# USB-Serial.net
KiCad netlist of a schematic drawn in Altium Designer
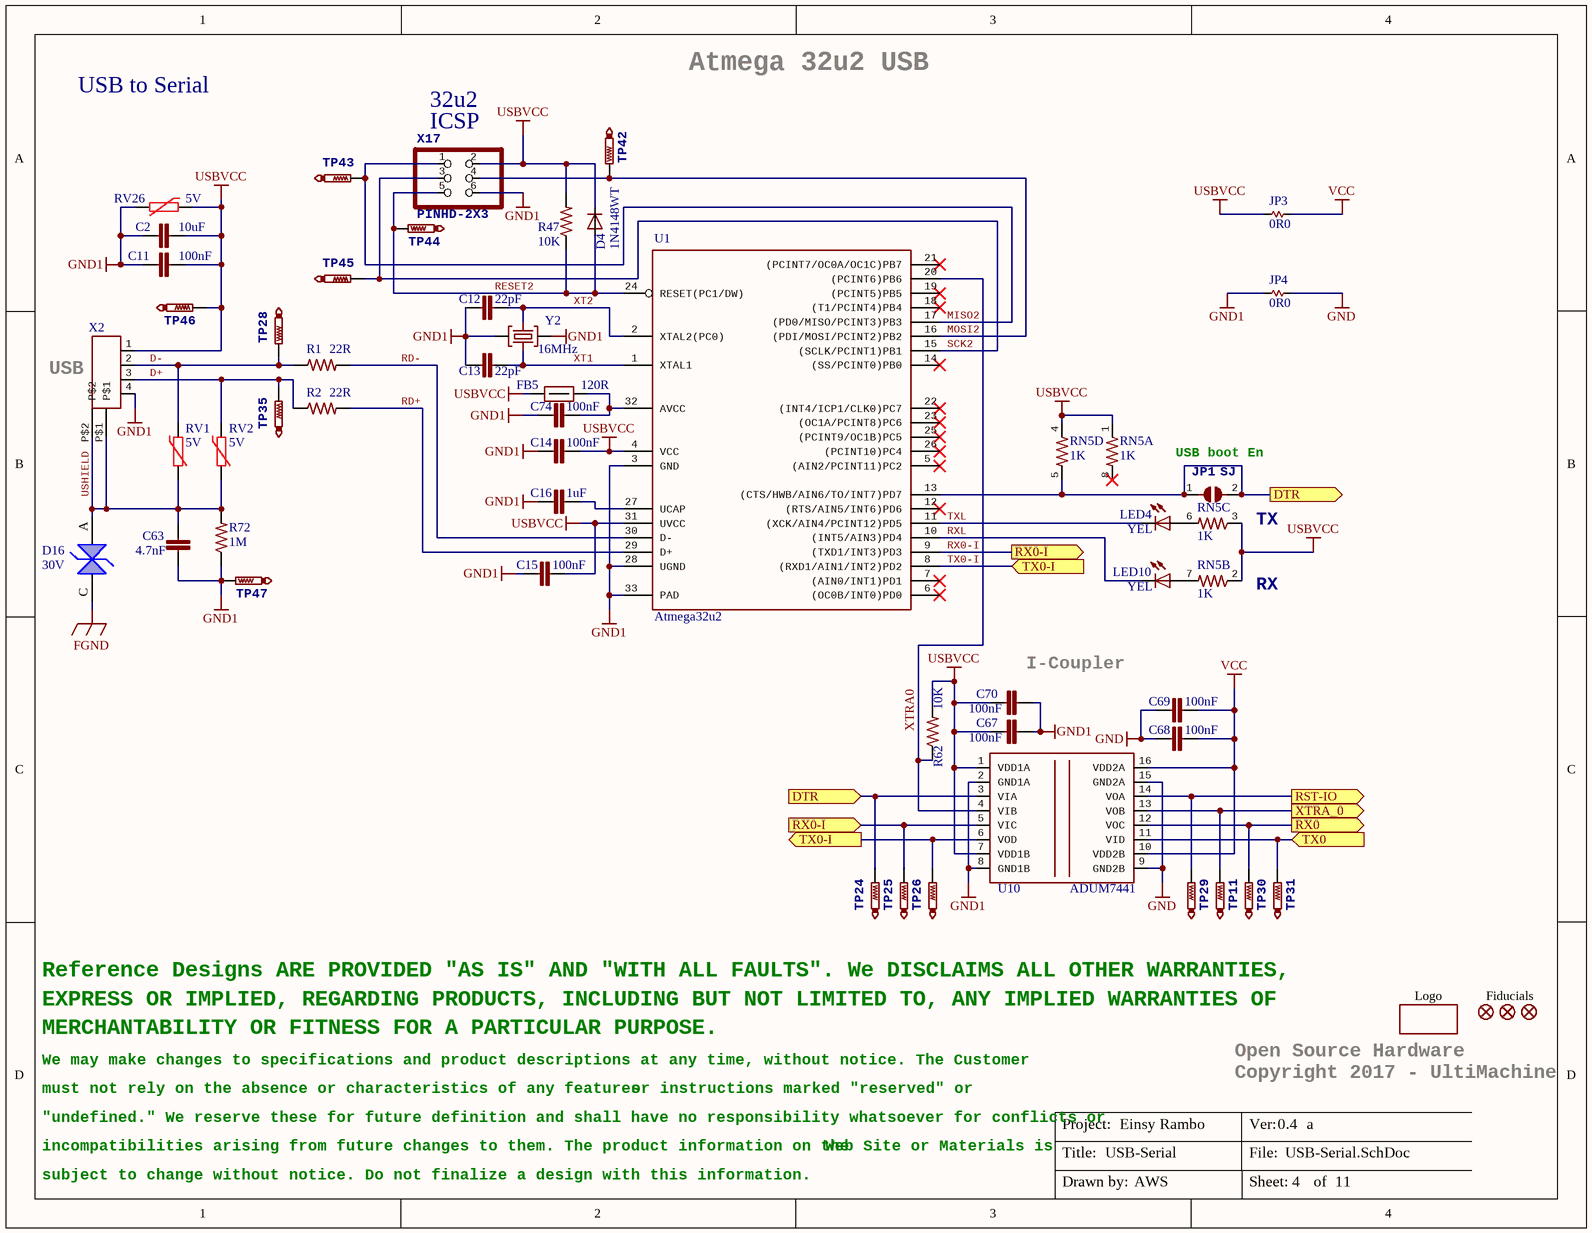
[diagram p0: USB-Serial.SchDoc]

(export (version "E")
  (design (tool "Eeschema 10.0.6"))
  (components
    (comp (ref "C2")
      (value "10uF")
      (footprint "C0805")
      (description "CAP CER 0805 10uF 10V 10% X5R")
      (fields (field (name "MANUFACTURER") "Kemet") (field (name "TOLERANCE") "+/- 10%"))
      (libsource (lib "3Delight") (part "C0805C106K8PACTU"))
    )
    (comp (ref "C11")
      (value "100nF")
      (footprint "C0402")
      (description "CAP CER 0402 100nF 16V 10% X7R")
      (fields (field (name "MANUFACTURER") "Murata") (field (name "TOLERANCE") "+/- 10%"))
      (libsource (lib "3Delight") (part "GRM155R71C104KA88D"))
    )
    (comp (ref "C12")
      (value "22pF")
      (footprint "C0402")
      (description "CAP CER 0402 22pF 50V 5% C0G")
      (fields (field (name "MANUFACTURER") "AVX") (field (name "PART") "22pF 50V"))
      (libsource (lib "3Delight") (part "04025A220JAT2A"))
    )
    (comp (ref "C13")
      (value "22pF")
      (footprint "C0402")
      (description "CAP CER 0402 22pF 50V 5% C0G")
      (fields (field (name "MANUFACTURER") "AVX") (field (name "PART") "22pF 50V"))
      (libsource (lib "3Delight") (part "04025A220JAT2A"))
    )
    (comp (ref "C14")
      (value "100nF")
      (footprint "C0402")
      (description "CAP CER 0402 100nF 16V 10% X7R")
      (fields (field (name "MANUFACTURER") "Murata") (field (name "TOLERANCE") "+/- 10%"))
      (libsource (lib "3Delight") (part "GRM155R71C104KA88D"))
    )
    (comp (ref "C15")
      (value "100nF")
      (footprint "C0402")
      (description "CAP CER 0402 100nF 16V 10% X7R")
      (fields (field (name "MANUFACTURER") "Murata") (field (name "TOLERANCE") "+/- 10%"))
      (libsource (lib "3Delight") (part "GRM155R71C104KA88D"))
    )
    (comp (ref "C16")
      (value "1uF")
      (footprint "C0402")
      (description "CAP CER 0402 1uF 6.3V 10% X5R")
      (fields (field (name "MANUFACTURER") "Murata") (field (name "TOLERANCE") "+/- 10%"))
      (libsource (lib "3Delight") (part "GRM155R60J105KE19D"))
    )
    (comp (ref "C63")
      (value "4.7nF")
      (footprint "C0402")
      (description "CAP CER 0402 4.7nF 25V 10% X7R")
      (fields (field (name "MANUFACTURER") "YAGEO") (field (name "TOLERANCE") "+/- 10%"))
      (libsource (lib "3Delight") (part "CC0402KRX7R8BB472"))
    )
    (comp (ref "C67")
      (value "100nF")
      (footprint "C0402")
      (description "CAP CER 0402 100nF 16V 10% X7R")
      (fields (field (name "MANUFACTURER") "Murata") (field (name "TOLERANCE") "+/- 10%"))
      (libsource (lib "3Delight") (part "GRM155R71C104KA88D"))
    )
    (comp (ref "C68")
      (value "100nF")
      (footprint "C0402")
      (description "CAP CER 0402 100nF 16V 10% X7R")
      (fields (field (name "MANUFACTURER") "Murata") (field (name "TOLERANCE") "+/- 10%"))
      (libsource (lib "") (part "GRM155R71C104KA88D_1"))
    )
    (comp (ref "C69")
      (value "100nF")
      (footprint "C0402")
      (description "CAP CER 0402 100nF 16V 10% X7R")
      (fields (field (name "MANUFACTURER") "Murata") (field (name "TOLERANCE") "+/- 10%"))
      (libsource (lib "3Delight") (part "GRM155R71C104KA88D"))
    )
    (comp (ref "C70")
      (value "100nF")
      (footprint "C0402")
      (description "CAP CER 0402 100nF 16V 10% X7R")
      (fields (field (name "MANUFACTURER") "Murata") (field (name "TOLERANCE") "+/- 10%"))
      (libsource (lib "") (part "GRM155R71C104KA88D_1"))
    )
    (comp (ref "C74")
      (value "100nF")
      (footprint "C0402")
      (description "CAP CER 0402 100nF 16V 10% X7R")
      (fields (field (name "MANUFACTURER") "Murata") (field (name "TOLERANCE") "+/- 10%"))
      (libsource (lib "3Delight") (part "GRM155R71C104KA88D"))
    )
    (comp (ref "D4")
      (value "1N4148WT")
      (footprint "SOD523")
      (description "DIODE SOD523")
      (fields (field (name "MANUFACTURER") "Fairchild") (field (name "TOLERANCE") "NA"))
      (libsource (lib "3Delight") (part "1N4148WT"))
    )
    (comp (ref "D16")
      (value "30V")
      (footprint "SOD323-R")
      (description "DIODE TVS")
      (fields (field (name "MANUFACTURER") "Rohm") (field (name "TOLERANCE") "NA"))
      (libsource (lib "3Delight") (part "RSB39VTE-17"))
    )
    (comp (ref "FB5")
      (value "120R")
      (footprint "FB0603")
      (description "FERRITE BEAD 120 OHM 0603 1LN")
      (fields (field (name "MANUFACTURER") "Samsung") (field (name "PART") "FERRITE 120R 3A 0603"))
      (libsource (lib "3Delight") (part "FERRITE 220R 2.5A 0603"))
    )
    (comp (ref "FID1")
      (value "FIDUCIAL")
      (footprint "FIDUCIAL-1X2")
      (description "Fiducial")
      (libsource (lib "3Delight") (part "FIDUCIAL"))
    )
    (comp (ref "FID2")
      (value "FIDUCIAL")
      (footprint "FIDUCIAL-1X2")
      (description "Fiducial")
      (libsource (lib "3Delight") (part "FIDUCIAL"))
    )
    (comp (ref "FID3")
      (value "FIDUCIAL")
      (footprint "FIDUCIAL-1X2")
      (description "Fiducial")
      (libsource (lib "3Delight") (part "FIDUCIAL"))
    )
    (comp (ref "JP1")
      (value "SJ")
      (footprint "SJ")
      (description "SMD solder jumper")
      (libsource (lib "3Delight") (part "SJ"))
    )
    (comp (ref "JP3")
      (value "0R0")
      (footprint "R0805")
      (description "RES 0.0 OHM 1/8W JUMP 0805 SMD")
      (fields (field (name "MANUFACTURER") "STACKPOLE") (field (name "TOLERANCE") "1%"))
      (libsource (lib "Resistors") (part "0R0 1% 0805"))
    )
    (comp (ref "JP4")
      (value "0R0")
      (footprint "R0805")
      (description "RES 0.0 OHM 1/8W JUMP 0805 SMD")
      (fields (field (name "MANUFACTURER") "STACKPOLE") (field (name "TOLERANCE") "1%"))
      (libsource (lib "Resistors") (part "0R0 1% 0805"))
    )
    (comp (ref "LED4")
      (value "YEL")
      (footprint "LED2012120")
      (description "LED 0805 Yellow")
      (fields (field (name "MANUFACTURER") "Dialight") (field (name "TOLERANCE") "NA"))
      (libsource (lib "3Delight") (part "5988140107F"))
    )
    (comp (ref "LED10")
      (value "YEL")
      (footprint "LED2012120")
      (description "LED 0805 Yellow")
      (fields (field (name "MANUFACTURER") "Dialight") (field (name "TOLERANCE") "NA"))
      (libsource (lib "3Delight") (part "5988140107F"))
    )
    (comp (ref "LOGO1")
      (value "OSHW_LOGO_8MILX0150-NT")
      (footprint "OSHW_8X150_NOTEXT")
      (libsource (lib "3Delight") (part "OSHW_LOGO_8MILX0150-NT"))
    )
    (comp (ref "R1")
      (value "22R")
      (footprint "R0402")
      (description "RES 0402 22r 62.5mW 1%")
      (fields (field (name "MANUFACTURER") "Yageo") (field (name "TOLERANCE") "+/- 1%"))
      (libsource (lib "3Delight") (part "RC0402FR-0722RL"))
    )
    (comp (ref "R2")
      (value "22R")
      (footprint "R0402")
      (description "RES 0402 22r 62.5mW 1%")
      (fields (field (name "MANUFACTURER") "Yageo") (field (name "TOLERANCE") "+/- 1%"))
      (libsource (lib "3Delight") (part "RC0402FR-0722RL"))
    )
    (comp (ref "R47")
      (value "10K")
      (footprint "R0402")
      (description "RES SMD 10K OHM 1% 1/16W 0402")
      (fields (field (name "MANUFACTURER") "Yageo") (field (name "PART") "10k 1% 0402"))
      (libsource (lib "3Delight") (part "RC0402FR-0710KP"))
    )
    (comp (ref "R62")
      (value "10K")
      (footprint "R0402")
      (description "RES SMD 10K OHM 1% 1/16W 0402")
      (fields (field (name "MANUFACTURER") "Yageo") (field (name "PART") "10k 1% 0402"))
      (libsource (lib "3Delight") (part "RC0402FR-0710KP"))
    )
    (comp (ref "R72")
      (value "1M")
      (footprint "R0402")
      (description "RES 0402 1M 100mW 5%")
      (fields (field (name "MANUFACTURER") "Panasonic") (field (name "TOLERANCE") "+/- 1%"))
      (libsource (lib "3Delight") (part "ERJ2GEJ105X"))
    )
    (comp (ref "RN5")
      (value "1K")
      (footprint "CAY16")
      (description "RES ARRAY 4 RES 1K 1206 62.5mW 5%")
      (fields (field (name "MANUFACTURER") "Bourns") (field (name "TOLERANCE") "+/- 5%"))
      (libsource (lib "3Delight") (part "CAY16-102J4LF"))
    )
    (comp (ref "RV1")
      (value "5V")
      (footprint "R0603")
      (description "VAR 0603 5V")
      (fields (field (name "MANUFACTURER") "YAGEO") (field (name "PART") "5VDC"))
      (libsource (lib "3Delight") (part "CG0603MLC-05E"))
    )
    (comp (ref "RV2")
      (value "5V")
      (footprint "R0603")
      (description "VAR 0603 5V")
      (fields (field (name "MANUFACTURER") "YAGEO") (field (name "PART") "5VDC"))
      (libsource (lib "3Delight") (part "CG0603MLC-05E"))
    )
    (comp (ref "RV26")
      (value "5V")
      (footprint "R0603")
      (description "VAR 0603 5V")
      (fields (field (name "MANUFACTURER") "YAGEO") (field (name "PART") "5VDC"))
      (libsource (lib "3Delight") (part "CG0603MLC-05E"))
    )
    (comp (ref "TP11")
      (value "TestPoint")
      (footprint "TP1-27")
      (description "Test Point")
      (libsource (lib "") (part "TestPoint_1"))
    )
    (comp (ref "TP24")
      (value "TestPoint")
      (footprint "TP1-27")
      (description "Test Point")
      (libsource (lib "") (part "TestPoint_1"))
    )
    (comp (ref "TP25")
      (value "TestPoint")
      (footprint "TP1-27")
      (description "Test Point")
      (libsource (lib "") (part "TestPoint_1"))
    )
    (comp (ref "TP26")
      (value "TestPoint")
      (footprint "TP1-27")
      (description "Test Point")
      (libsource (lib "") (part "TestPoint_1"))
    )
    (comp (ref "TP28")
      (value "TestPoint")
      (footprint "TP1-27")
      (description "Test Point")
      (libsource (lib "3Delight") (part "TestPoint"))
    )
    (comp (ref "TP29")
      (value "TestPoint")
      (footprint "TP1-27")
      (description "Test Point")
      (libsource (lib "") (part "TestPoint_1"))
    )
    (comp (ref "TP30")
      (value "TestPoint")
      (footprint "TP1-27")
      (description "Test Point")
      (libsource (lib "") (part "TestPoint_1"))
    )
    (comp (ref "TP31")
      (value "TestPoint")
      (footprint "TP1-27")
      (description "Test Point")
      (libsource (lib "") (part "TestPoint_1"))
    )
    (comp (ref "TP35")
      (value "TestPoint")
      (footprint "TP1-27")
      (description "Test Point")
      (libsource (lib "") (part "TestPoint_1"))
    )
    (comp (ref "TP42")
      (value "TestPoint")
      (footprint "TP1-27")
      (description "Test Point")
      (libsource (lib "3Delight") (part "TestPoint"))
    )
    (comp (ref "TP43")
      (value "TestPoint")
      (footprint "TP1-27")
      (description "Test Point")
      (libsource (lib "") (part "TestPoint_2"))
    )
    (comp (ref "TP44")
      (value "TestPoint")
      (footprint "TP1-27")
      (description "Test Point")
      (libsource (lib "") (part "TestPoint_3"))
    )
    (comp (ref "TP45")
      (value "TestPoint")
      (footprint "TP1-27")
      (description "Test Point")
      (libsource (lib "") (part "TestPoint_2"))
    )
    (comp (ref "TP46")
      (value "TestPoint")
      (footprint "TP1-27")
      (description "Test Point")
      (libsource (lib "") (part "TestPoint_2"))
    )
    (comp (ref "TP47")
      (value "TestPoint")
      (footprint "TP1-27")
      (description "Test Point")
      (libsource (lib "") (part "TestPoint_3"))
    )
    (comp (ref "U1")
      (value "Atmega32u2")
      (footprint "QFN32_DualSolderMask")
      (fields
        (field (name "MANUFACTURER") "Microchip")
        (field (name "PART") "ATMEGA32U2")
        (field (name "TOLERANCE") "NA")
      )
      (libsource (lib "ICs-uC") (part "ATMEGA32U2-DualSolderMask"))
    )
    (comp (ref "U10")
      (value "ADUM7441")
      (footprint "QSOP16")
      (description "4ch iCoupler")
      (fields (field (name "MANUFACTURER") "Analog Devices") (field (name "PART") "ADUM7441ARQZ"))
      (libsource (lib "3Delight") (part "ADUM7441"))
    )
    (comp (ref "X2")
      (value "USB-B")
      (footprint "PN61729")
      (description "USB connector B PTH")
      (fields (field (name "MANUFACTURER") "FCI") (field (name "TOLERANCE") "NA"))
      (libsource (lib "3Delight") (part "USB-B"))
    )
    (comp (ref "X17")
      (value "PINHD-2X3")
      (footprint "2X03")
      (description "CONN HEADER VERT 6POS GOLD")
      (fields (field (name "MANUFACTURER") "MultiComp") (field (name "PART") "6PIN"))
      (libsource (lib "Connectors") (part "PINHD-2X3"))
    )
    (comp (ref "Y2")
      (value "16MHz")
      (footprint "CRYS320250")
      (description "Crystal 16mHz 10ppm 10pF")
      (fields (field (name "MANUFACTURER") "TXC") (field (name "TOLERANCE") "10ppm"))
      (libsource (lib "3Delight") (part "7M-16.000MEEQ-T"))
    )
  )
  (nets
    (net (code "1") (name "/D+") (class "Default")
      (node (ref "R2") (pin "1") (pinfunction "1_1") (pintype "passive"))
      (node (ref "RV2") (pin "2") (pinfunction "2_2") (pintype "passive"))
      (node (ref "TP35") (pin "TP") (pinfunction "TP_TP") (pintype "passive"))
      (node (ref "X2") (pin "3") (pinfunction "3_3") (pintype "passive"))
    )
    (net (code "2") (name "/D-") (class "Default")
      (node (ref "R1") (pin "1") (pinfunction "1_1") (pintype "passive"))
      (node (ref "RV1") (pin "2") (pinfunction "2_2") (pintype "passive"))
      (node (ref "TP28") (pin "TP") (pinfunction "TP_TP") (pintype "passive"))
      (node (ref "X2") (pin "2") (pinfunction "2_2") (pintype "passive"))
    )
    (net (code "3") (name "/DTR") (class "Default")
      (node (ref "JP1") (pin "1") (pinfunction "1_1") (pintype "passive"))
      (node (ref "JP1") (pin "2") (pinfunction "2_2") (pintype "passive"))
      (node (ref "RN5") (pin "5") (pinfunction "2_5") (pintype "passive"))
      (node (ref "TP24") (pin "TP") (pinfunction "TP_TP") (pintype "passive"))
      (node (ref "U1") (pin "13") (pinfunction "(CTS/HWB/AIN6/TO/INT7)PD7_13") (pintype "passive"))
      (node (ref "U10") (pin "3") (pinfunction "VIA_3") (pintype "passive"))
    )
    (net (code "4") (name "/MISO2") (class "Default")
      (node (ref "TP43") (pin "TP") (pinfunction "TP_TP") (pintype "passive"))
      (node (ref "U1") (pin "17") (pinfunction "(PD0/MISO/PCINT3)PB3_17") (pintype "passive"))
      (node (ref "X17") (pin "1") (pinfunction "1_1") (pintype "passive"))
    )
    (net (code "5") (name "/MOSI2") (class "Default")
      (node (ref "TP42") (pin "TP") (pinfunction "TP_TP") (pintype "passive"))
      (node (ref "U1") (pin "16") (pinfunction "(PDI/MOSI/PCINT2)PB2_16") (pintype "passive"))
      (node (ref "X17") (pin "4") (pinfunction "4_4") (pintype "passive"))
    )
    (net (code "6") (name "/RD+") (class "Default")
      (node (ref "R2") (pin "2") (pinfunction "2_2") (pintype "passive"))
      (node (ref "U1") (pin "29") (pinfunction "D+_29") (pintype "passive"))
    )
    (net (code "7") (name "/RD-") (class "Default")
      (node (ref "R1") (pin "2") (pinfunction "2_2") (pintype "passive"))
      (node (ref "U1") (pin "30") (pinfunction "D-_30") (pintype "passive"))
    )
    (net (code "8") (name "/RESET2") (class "Default")
      (node (ref "D4") (pin "A") (pinfunction "A_A") (pintype "passive"))
      (node (ref "R47") (pin "1") (pinfunction "1_1") (pintype "passive"))
      (node (ref "TP44") (pin "TP") (pinfunction "TP_TP") (pintype "passive"))
      (node (ref "U1") (pin "24") (pinfunction "RESET(PC1/DW)_24") (pintype "passive"))
      (node (ref "X17") (pin "5") (pinfunction "5_5") (pintype "passive"))
    )
    (net (code "9") (name "/RST-IO") (class "Default")
      (node (ref "TP29") (pin "TP") (pinfunction "TP_TP") (pintype "passive"))
      (node (ref "U10") (pin "14") (pinfunction "VOA_14") (pintype "passive"))
    )
    (net (code "10") (name "/RX0") (class "Default")
      (node (ref "TP30") (pin "TP") (pinfunction "TP_TP") (pintype "passive"))
      (node (ref "U10") (pin "12") (pinfunction "VOC_12") (pintype "passive"))
    )
    (net (code "11") (name "/RX0-I") (class "Default")
      (node (ref "TP25") (pin "TP") (pinfunction "TP_TP") (pintype "passive"))
      (node (ref "U1") (pin "9") (pinfunction "(TXD1/INT3)PD3_9") (pintype "passive"))
      (node (ref "U10") (pin "5") (pinfunction "VIC_5") (pintype "passive"))
    )
    (net (code "12") (name "/RXL") (class "Default")
      (node (ref "LED10") (pin "C") (pinfunction "C_C") (pintype "passive"))
      (node (ref "U1") (pin "10") (pinfunction "(INT5/AIN3)PD4_10") (pintype "passive"))
    )
    (net (code "13") (name "/SCK2") (class "Default")
      (node (ref "TP45") (pin "TP") (pinfunction "TP_TP") (pintype "passive"))
      (node (ref "U1") (pin "15") (pinfunction "(SCLK/PCINT1)PB1_15") (pintype "passive"))
      (node (ref "X17") (pin "3") (pinfunction "3_3") (pintype "passive"))
    )
    (net (code "14") (name "/TX0") (class "Default")
      (node (ref "TP31") (pin "TP") (pinfunction "TP_TP") (pintype "passive"))
      (node (ref "U10") (pin "11") (pinfunction "VID_11") (pintype "passive"))
    )
    (net (code "15") (name "/TX0-I") (class "Default")
      (node (ref "TP26") (pin "TP") (pinfunction "TP_TP") (pintype "passive"))
      (node (ref "U1") (pin "8") (pinfunction "(RXD1/AIN1/INT2)PD2_8") (pintype "passive"))
      (node (ref "U10") (pin "6") (pinfunction "VOD_6") (pintype "passive"))
    )
    (net (code "16") (name "/TXL") (class "Default")
      (node (ref "LED4") (pin "C") (pinfunction "C_C") (pintype "passive"))
      (node (ref "U1") (pin "11") (pinfunction "(XCK/AIN4/PCINT12)PD5_11") (pintype "passive"))
    )
    (net (code "17") (name "/USHIELD") (class "Default")
      (node (ref "C63") (pin "1") (pinfunction "1_1") (pintype "passive"))
      (node (ref "D16") (pin "A") (pinfunction "A_A") (pintype "power_in"))
      (node (ref "R72") (pin "2") (pinfunction "2_2") (pintype "passive"))
      (node (ref "RV1") (pin "1") (pinfunction "1_1") (pintype "passive"))
      (node (ref "RV2") (pin "1") (pinfunction "1_1") (pintype "passive"))
      (node (ref "X2") (pin "P$1") (pinfunction "P$1_P$1") (pintype "passive"))
      (node (ref "X2") (pin "P$2") (pinfunction "P$2_P$2") (pintype "passive"))
    )
    (net (code "18") (name "/XT1") (class "Default")
      (node (ref "C13") (pin "1") (pinfunction "1_1") (pintype "passive"))
      (node (ref "U1") (pin "1") (pinfunction "XTAL1_1") (pintype "passive"))
      (node (ref "Y2") (pin "1") (pinfunction "C1_1") (pintype "passive"))
    )
    (net (code "19") (name "/XT2") (class "Default")
      (node (ref "C12") (pin "1") (pinfunction "1_1") (pintype "passive"))
      (node (ref "U1") (pin "2") (pinfunction "XTAL2(PC0)_2") (pintype "passive"))
      (node (ref "Y2") (pin "3") (pinfunction "C2_3") (pintype "passive"))
    )
    (net (code "20") (name "/XTRA0") (class "Default")
      (node (ref "R62") (pin "1") (pinfunction "1_1") (pintype "passive"))
      (node (ref "U1") (pin "20") (pinfunction "(PCINT6)PB6_20") (pintype "passive"))
      (node (ref "U10") (pin "4") (pinfunction "VIB_4") (pintype "passive"))
    )
    (net (code "21") (name "/XTRA_0") (class "Default")
      (node (ref "TP11") (pin "TP") (pinfunction "TP_TP") (pintype "passive"))
      (node (ref "U10") (pin "13") (pinfunction "VOB_13") (pintype "passive"))
    )
    (net (code "22") (name "FGND") (class "Default")
      (node (ref "D16") (pin "C") (pinfunction "C_C") (pintype "power_in"))
    )
    (net (code "23") (name "GND") (class "Default")
      (node (ref "C68") (pin "1") (pinfunction "1_1") (pintype "passive"))
      (node (ref "C69") (pin "2") (pinfunction "2_2") (pintype "passive"))
      (node (ref "JP4") (pin "2") (pinfunction "2_2") (pintype "passive"))
      (node (ref "U10") (pin "15") (pinfunction "GND2A_15") (pintype "passive"))
      (node (ref "U10") (pin "9") (pinfunction "GND2B_9") (pintype "passive"))
    )
    (net (code "24") (name "GND1") (class "Default")
      (node (ref "C11") (pin "2") (pinfunction "2_2") (pintype "passive"))
      (node (ref "C12") (pin "2") (pinfunction "2_2") (pintype "passive"))
      (node (ref "C13") (pin "2") (pinfunction "2_2") (pintype "passive"))
      (node (ref "C14") (pin "2") (pinfunction "2_2") (pintype "passive"))
      (node (ref "C15") (pin "2") (pinfunction "2_2") (pintype "passive"))
      (node (ref "C16") (pin "2") (pinfunction "2_2") (pintype "passive"))
      (node (ref "C2") (pin "1") (pinfunction "1_1") (pintype "passive"))
      (node (ref "C63") (pin "2") (pinfunction "2_2") (pintype "passive"))
      (node (ref "C67") (pin "1") (pinfunction "1_1") (pintype "passive"))
      (node (ref "C70") (pin "2") (pinfunction "2_2") (pintype "passive"))
      (node (ref "C74") (pin "2") (pinfunction "2_2") (pintype "passive"))
      (node (ref "JP4") (pin "1") (pinfunction "1_1") (pintype "passive"))
      (node (ref "R72") (pin "1") (pinfunction "1_1") (pintype "passive"))
      (node (ref "RV26") (pin "1") (pinfunction "1_1") (pintype "passive"))
      (node (ref "TP47") (pin "TP") (pinfunction "TP_TP") (pintype "passive"))
      (node (ref "U1") (pin "28") (pinfunction "UGND_28") (pintype "power_in"))
      (node (ref "U1") (pin "3") (pinfunction "GND_3") (pintype "power_in"))
      (node (ref "U1") (pin "33") (pinfunction "PAD_33") (pintype "power_in"))
      (node (ref "U10") (pin "2") (pinfunction "GND1A_2") (pintype "passive"))
      (node (ref "U10") (pin "8") (pinfunction "GND1B_8") (pintype "passive"))
      (node (ref "X17") (pin "6") (pinfunction "6_6") (pintype "passive"))
      (node (ref "X2") (pin "4") (pinfunction "4_4") (pintype "passive"))
      (node (ref "Y2") (pin "2") (pinfunction "GND_2") (pintype "passive"))
      (node (ref "Y2") (pin "4") (pinfunction "GND_4") (pintype "passive"))
    )
    (net (code "25") (name "Net-(RN5B-2)") (class "Default")
      (node (ref "LED10") (pin "A") (pinfunction "A_A") (pintype "passive"))
      (node (ref "RN5") (pin "7") (pinfunction "2_7") (pintype "passive"))
    )
    (net (code "26") (name "Net-(RN5C-2)") (class "Default")
      (node (ref "LED4") (pin "A") (pinfunction "A_A") (pintype "passive"))
      (node (ref "RN5") (pin "6") (pinfunction "2_6") (pintype "passive"))
    )
    (net (code "27") (name "Net-(U1-AVCC)") (class "Default")
      (node (ref "C74") (pin "1") (pinfunction "1_1") (pintype "passive"))
      (node (ref "FB5") (pin "2") (pinfunction "2_2") (pintype "passive"))
      (node (ref "U1") (pin "32") (pinfunction "AVCC_32") (pintype "power_in"))
    )
    (net (code "28") (name "Net-(U1-UCAP)") (class "Default")
      (node (ref "C16") (pin "1") (pinfunction "1_1") (pintype "passive"))
      (node (ref "U1") (pin "27") (pinfunction "UCAP_27") (pintype "passive"))
    )
    (net (code "29") (name "USBVCC") (class "Default")
      (node (ref "C11") (pin "1") (pinfunction "1_1") (pintype "passive"))
      (node (ref "C14") (pin "1") (pinfunction "1_1") (pintype "passive"))
      (node (ref "C15") (pin "1") (pinfunction "1_1") (pintype "passive"))
      (node (ref "C2") (pin "2") (pinfunction "2_2") (pintype "passive"))
      (node (ref "C67") (pin "2") (pinfunction "2_2") (pintype "passive"))
      (node (ref "C70") (pin "1") (pinfunction "1_1") (pintype "passive"))
      (node (ref "D4") (pin "C") (pinfunction "C_C") (pintype "passive"))
      (node (ref "FB5") (pin "1") (pinfunction "1_1") (pintype "passive"))
      (node (ref "JP3") (pin "1") (pinfunction "1_1") (pintype "passive"))
      (node (ref "R47") (pin "2") (pinfunction "2_2") (pintype "passive"))
      (node (ref "R62") (pin "2") (pinfunction "2_2") (pintype "passive"))
      (node (ref "RN5") (pin "1") (pinfunction "1_1") (pintype "passive"))
      (node (ref "RN5") (pin "2") (pinfunction "1_2") (pintype "passive"))
      (node (ref "RN5") (pin "3") (pinfunction "1_3") (pintype "passive"))
      (node (ref "RN5") (pin "4") (pinfunction "1_4") (pintype "passive"))
      (node (ref "RV26") (pin "2") (pinfunction "2_2") (pintype "passive"))
      (node (ref "TP46") (pin "TP") (pinfunction "TP_TP") (pintype "passive"))
      (node (ref "U1") (pin "31") (pinfunction "UVCC_31") (pintype "power_in"))
      (node (ref "U1") (pin "4") (pinfunction "VCC_4") (pintype "power_in"))
      (node (ref "U10") (pin "1") (pinfunction "VDD1A_1") (pintype "passive"))
      (node (ref "U10") (pin "7") (pinfunction "VDD1B_7") (pintype "passive"))
      (node (ref "X17") (pin "2") (pinfunction "2_2") (pintype "passive"))
      (node (ref "X2") (pin "1") (pinfunction "1_1") (pintype "passive"))
    )
    (net (code "30") (name "VCC") (class "Default")
      (node (ref "C68") (pin "2") (pinfunction "2_2") (pintype "passive"))
      (node (ref "C69") (pin "1") (pinfunction "1_1") (pintype "passive"))
      (node (ref "JP3") (pin "2") (pinfunction "2_2") (pintype "passive"))
      (node (ref "U10") (pin "10") (pinfunction "VDD2B_10") (pintype "passive"))
      (node (ref "U10") (pin "16") (pinfunction "VDD2A_16") (pintype "passive"))
    )
    (net (code "31") (name "unconnected-(RN5A-2-Pad8)") (class "Default")
      (node (ref "RN5") (pin "8") (pinfunction "2_8") (pintype "passive+no_connect"))
    )
    (net (code "32") (name "unconnected-(U1-(AIN0{slash}INT1)PD1-Pad7)") (class "Default")
      (node (ref "U1") (pin "7") (pinfunction "(AIN0/INT1)PD1_7") (pintype "passive+no_connect"))
    )
    (net (code "33") (name "unconnected-(U1-(AIN2{slash}PCINT11)PC2-Pad5)") (class "Default")
      (node (ref "U1") (pin "5") (pinfunction "(AIN2/PCINT11)PC2_5") (pintype "passive+no_connect"))
    )
    (net (code "34") (name "unconnected-(U1-(INT4{slash}ICP1{slash}CLK0)PC7-Pad22)") (class "Default")
      (node (ref "U1") (pin "22") (pinfunction "(INT4/ICP1/CLK0)PC7_22") (pintype "passive+no_connect"))
    )
    (net (code "35") (name "unconnected-(U1-(OC0B{slash}INT0)PD0-Pad6)") (class "Default")
      (node (ref "U1") (pin "6") (pinfunction "(OC0B/INT0)PD0_6") (pintype "passive+no_connect"))
    )
    (net (code "36") (name "unconnected-(U1-(OC1A{slash}PCINT8)PC6-Pad23)") (class "Default")
      (node (ref "U1") (pin "23") (pinfunction "(OC1A/PCINT8)PC6_23") (pintype "passive+no_connect"))
    )
    (net (code "37") (name "unconnected-(U1-(PCINT5)PB5-Pad19)") (class "Default")
      (node (ref "U1") (pin "19") (pinfunction "(PCINT5)PB5_19") (pintype "passive+no_connect"))
    )
    (net (code "38") (name "unconnected-(U1-(PCINT7{slash}OC0A{slash}OC1C)PB7-Pad21)") (class "Default")
      (node (ref "U1") (pin "21") (pinfunction "(PCINT7/OC0A/OC1C)PB7_21") (pintype "passive+no_connect"))
    )
    (net (code "39") (name "unconnected-(U1-(PCINT9{slash}OC1B)PC5-Pad25)") (class "Default")
      (node (ref "U1") (pin "25") (pinfunction "(PCINT9/OC1B)PC5_25") (pintype "passive+no_connect"))
    )
    (net (code "40") (name "unconnected-(U1-(PCINT10)PC4-Pad26)") (class "Default")
      (node (ref "U1") (pin "26") (pinfunction "(PCINT10)PC4_26") (pintype "passive+no_connect"))
    )
    (net (code "41") (name "unconnected-(U1-(RTS{slash}AIN5{slash}INT6)PD6-Pad12)") (class "Default")
      (node (ref "U1") (pin "12") (pinfunction "(RTS/AIN5/INT6)PD6_12") (pintype "passive+no_connect"))
    )
    (net (code "42") (name "unconnected-(U1-(SS{slash}PCINT0)PB0-Pad14)") (class "Default")
      (node (ref "U1") (pin "14") (pinfunction "(SS/PCINT0)PB0_14") (pintype "passive+no_connect"))
    )
    (net (code "43") (name "unconnected-(U1-(T1{slash}PCINT4)PB4-Pad18)") (class "Default")
      (node (ref "U1") (pin "18") (pinfunction "(T1/PCINT4)PB4_18") (pintype "passive+no_connect"))
    )
  )
)
